# super-serial.net
KiCad netlist of a schematic drawn in EAGLE
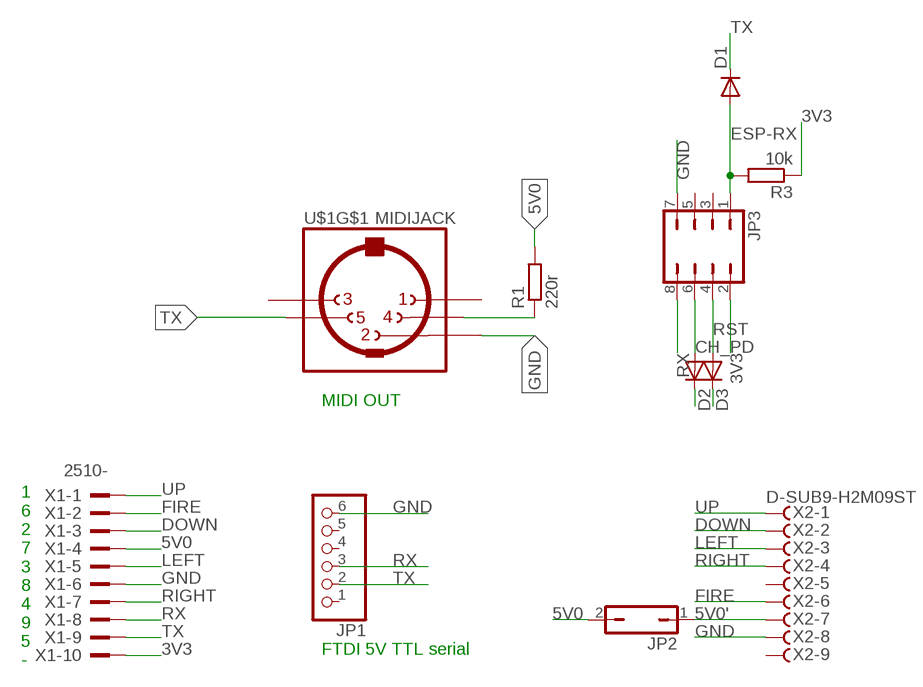
[diagram p0: schematic, sheet 1]

(export (version "E")
  (design (tool "Eeschema 10.0.6"))
  (components
    (comp (ref "D1")
      (value "DIODEDO-1N4148")
      (footprint "eagle-import:DO-1N4148")
      (libsource (lib "eagle-import") (part "DIODEDO-1N4148"))
    )
    (comp (ref "D2")
      (value "DIODEDO-1N4148")
      (footprint "eagle-import:DO-1N4148")
      (libsource (lib "eagle-import") (part "DIODEDO-1N4148"))
    )
    (comp (ref "D3")
      (value "DIODEDO-1N4148")
      (footprint "eagle-import:DO-1N4148")
      (libsource (lib "eagle-import") (part "DIODEDO-1N4148"))
    )
    (comp (ref "JP1")
      (value "PINHD-1X6CB")
      (footprint "eagle-import:1X06-CLEANBIG")
      (libsource (lib "eagle-import") (part "PINHD-1X6CB"))
    )
    (comp (ref "JP2")
      (value "JP1Q")
      (footprint "eagle-import:JP1")
      (libsource (lib "eagle-import") (part "JP1Q"))
    )
    (comp (ref "JP3")
      (value "JP4Q")
      (footprint "eagle-import:JP4Q")
      (libsource (lib "eagle-import") (part "JP4Q"))
    )
    (comp (ref "R1")
      (value "220r")
      (footprint "eagle-import:0204_7")
      (libsource (lib "eagle-import") (part "R-EU_0204/7"))
    )
    (comp (ref "R3")
      (value "10k")
      (footprint "eagle-import:0204_7")
      (libsource (lib "eagle-import") (part "R-EU_0204/7"))
    )
    (comp (ref "U$1")
      (value "MIDIJACK")
      (footprint "eagle-import:CP-2350")
      (libsource (lib "eagle-import") (part "MIDIJACK"))
    )
    (comp (ref "X1")
      (value "2510-")
      (footprint "eagle-import:PAK100_2500-10")
      (fields (field (name "MF") "3M") (field (name "MPN") "2510-6002UB"))
      (libsource (lib "eagle-import") (part "2510-"))
    )
    (comp (ref "X2")
      (value "D-SUB9-H2M09ST")
      (footprint "eagle-import:H2M09ST")
      (libsource (lib "eagle-import") (part "D-SUB9-H2M09ST"))
    )
  )
  (nets
    (net (code "1") (name "/3V3") (class "Default")
      (node (ref "JP3") (pin "2") (pinfunction "2_2") (pintype "passive"))
      (node (ref "R3") (pin "1") (pinfunction "1_1") (pintype "passive"))
      (node (ref "X1") (pin "10") (pinfunction "KL_10") (pintype "passive"))
    )
    (net (code "2") (name "/5V0'") (class "Default")
      (node (ref "JP2") (pin "1") (pinfunction "1_1") (pintype "passive"))
      (node (ref "X2") (pin "7") (pinfunction "F_7") (pintype "passive"))
    )
    (net (code "3") (name "/CH_PD") (class "Default")
      (node (ref "D2") (pin "A") (pinfunction "A_A") (pintype "passive"))
      (node (ref "JP3") (pin "6") (pinfunction "6_6") (pintype "passive"))
    )
    (net (code "4") (name "/DOWN") (class "Default")
      (node (ref "X1") (pin "3") (pinfunction "KL_3") (pintype "passive"))
      (node (ref "X2") (pin "2") (pinfunction "F_2") (pintype "passive"))
    )
    (net (code "5") (name "/ESP-RX") (class "Default")
      (node (ref "D1") (pin "A") (pinfunction "A_A") (pintype "passive"))
      (node (ref "JP3") (pin "1") (pinfunction "1_1") (pintype "passive"))
      (node (ref "R3") (pin "2") (pinfunction "2_2") (pintype "passive"))
    )
    (net (code "6") (name "/FIRE") (class "Default")
      (node (ref "D3") (pin "C") (pinfunction "C_C") (pintype "passive"))
      (node (ref "X1") (pin "2") (pinfunction "KL_2") (pintype "passive"))
      (node (ref "X2") (pin "6") (pinfunction "F_6") (pintype "passive"))
    )
    (net (code "7") (name "/LEFT") (class "Default")
      (node (ref "X1") (pin "5") (pinfunction "KL_5") (pintype "passive"))
      (node (ref "X2") (pin "3") (pinfunction "F_3") (pintype "passive"))
    )
    (net (code "8") (name "/RIGHT") (class "Default")
      (node (ref "X1") (pin "7") (pinfunction "KL_7") (pintype "passive"))
      (node (ref "X2") (pin "4") (pinfunction "F_4") (pintype "passive"))
    )
    (net (code "9") (name "/RST") (class "Default")
      (node (ref "D3") (pin "A") (pinfunction "A_A") (pintype "passive"))
      (node (ref "JP3") (pin "4") (pinfunction "4_4") (pintype "passive"))
    )
    (net (code "10") (name "/RX") (class "Default")
      (node (ref "JP1") (pin "3") (pinfunction "3_3") (pintype "passive"))
      (node (ref "JP3") (pin "8") (pinfunction "8_8") (pintype "passive"))
      (node (ref "X1") (pin "8") (pinfunction "KL_8") (pintype "passive"))
    )
    (net (code "11") (name "/UP") (class "Default")
      (node (ref "D2") (pin "C") (pinfunction "C_C") (pintype "passive"))
      (node (ref "X1") (pin "1") (pinfunction "KL_1") (pintype "passive"))
      (node (ref "X2") (pin "1") (pinfunction "F_1") (pintype "passive"))
    )
    (net (code "12") (name "5V0") (class "Default")
      (node (ref "JP2") (pin "2") (pinfunction "2_2") (pintype "passive"))
      (node (ref "R1") (pin "2") (pinfunction "2_2") (pintype "passive"))
      (node (ref "X1") (pin "4") (pinfunction "KL_4") (pintype "passive"))
    )
    (net (code "13") (name "GND") (class "Default")
      (node (ref "JP1") (pin "6") (pinfunction "6_6") (pintype "passive"))
      (node (ref "JP3") (pin "7") (pinfunction "7_7") (pintype "passive"))
      (node (ref "U$1") (pin "2") (pinfunction "2_2") (pintype "passive"))
      (node (ref "X1") (pin "6") (pinfunction "KL_6") (pintype "passive"))
      (node (ref "X2") (pin "8") (pinfunction "F_8") (pintype "passive"))
    )
    (net (code "14") (name "Net-(R1-Pad1)") (class "Default")
      (node (ref "R1") (pin "1") (pinfunction "1_1") (pintype "passive"))
      (node (ref "U$1") (pin "4") (pinfunction "4_4") (pintype "passive"))
    )
    (net (code "15") (name "TX") (class "Default")
      (node (ref "D1") (pin "C") (pinfunction "C_C") (pintype "passive"))
      (node (ref "JP1") (pin "2") (pinfunction "2_2") (pintype "passive"))
      (node (ref "U$1") (pin "5") (pinfunction "5_5") (pintype "passive"))
      (node (ref "X1") (pin "9") (pinfunction "KL_9") (pintype "passive"))
    )
    (net (code "16") (name "unconnected-(JP1-Pad1)") (class "Default")
      (node (ref "JP1") (pin "1") (pinfunction "1_1") (pintype "passive"))
    )
    (net (code "17") (name "unconnected-(JP1-Pad4)") (class "Default")
      (node (ref "JP1") (pin "4") (pinfunction "4_4") (pintype "passive"))
    )
    (net (code "18") (name "unconnected-(JP1-Pad5)") (class "Default")
      (node (ref "JP1") (pin "5") (pinfunction "5_5") (pintype "passive"))
    )
    (net (code "19") (name "unconnected-(JP3-Pad3)") (class "Default")
      (node (ref "JP3") (pin "3") (pinfunction "3_3") (pintype "passive"))
    )
    (net (code "20") (name "unconnected-(JP3-Pad5)") (class "Default")
      (node (ref "JP3") (pin "5") (pinfunction "5_5") (pintype "passive"))
    )
    (net (code "21") (name "unconnected-(U$1-Pad1)") (class "Default")
      (node (ref "U$1") (pin "1") (pinfunction "1_1") (pintype "passive"))
    )
    (net (code "22") (name "unconnected-(U$1-Pad3)") (class "Default")
      (node (ref "U$1") (pin "3") (pinfunction "3_3") (pintype "passive"))
    )
    (net (code "23") (name "unconnected-(X2E-F-Pad5)") (class "Default")
      (node (ref "X2") (pin "5") (pinfunction "F_5") (pintype "passive"))
    )
    (net (code "24") (name "unconnected-(X2I-F-Pad9)") (class "Default")
      (node (ref "X2") (pin "9") (pinfunction "F_9") (pintype "passive"))
    )
  )
)
